# zulu_a7_6.net
KiCad netlist of a schematic drawn in Altium Designer
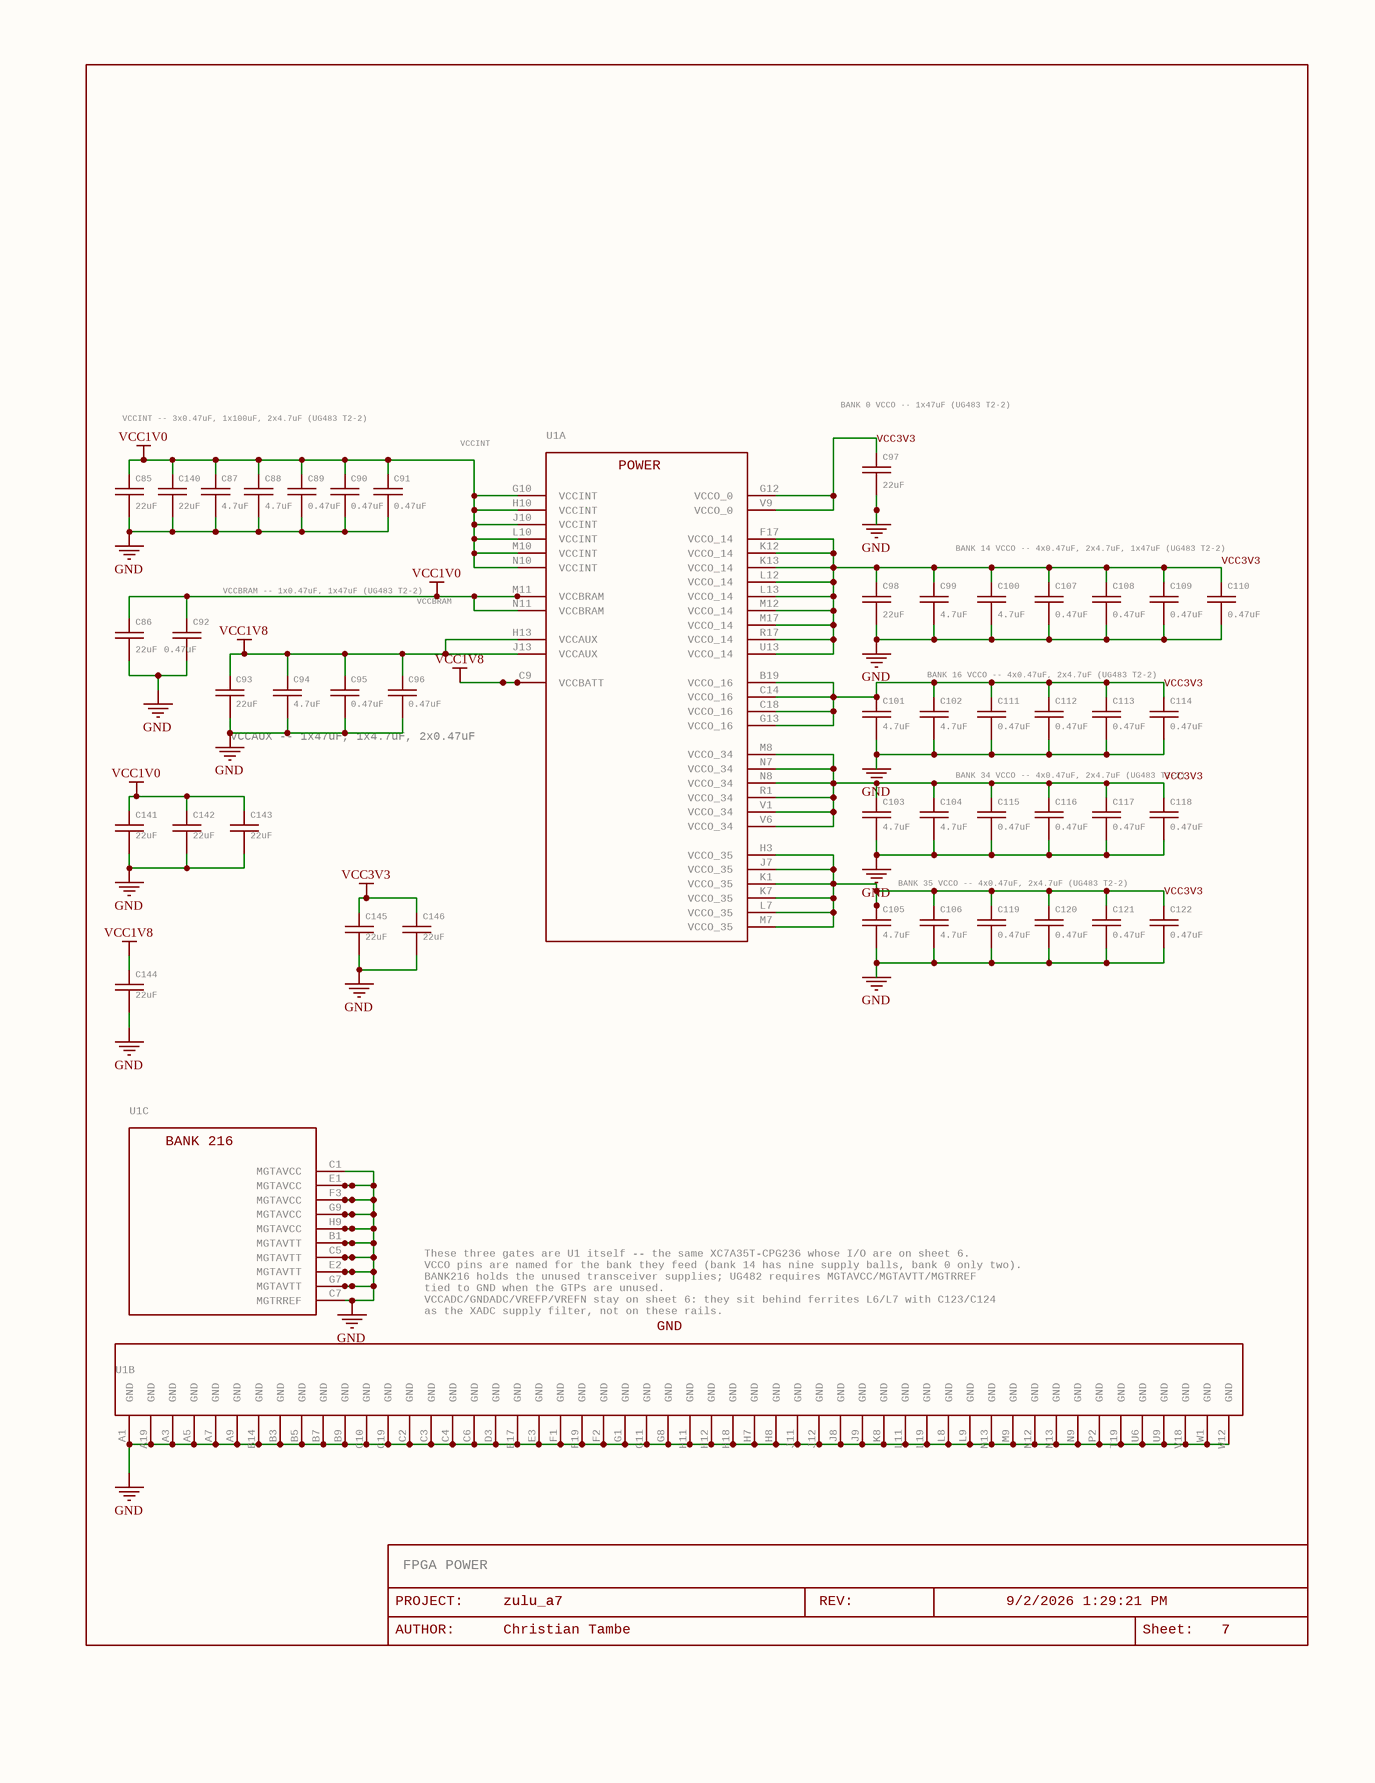
[diagram p0: zulu_a7_6.SchDoc]

(export (version "E")
  (design (tool "Eeschema 10.0.6"))
  (components
    (comp (ref "C85")
      (value "22uF")
      (footprint "C0805")
      (description "CAPACITOR, American symbol")
      (fields (field (name "MANF") "Murata"))
      (libsource (lib "") (part "C-USC0805_1"))
    )
    (comp (ref "C86")
      (value "22uF")
      (footprint "C0805")
      (description "CAPACITOR, American symbol")
      (fields (field (name "MANF") "Murata"))
      (libsource (lib "") (part "C-USC0805_1"))
    )
    (comp (ref "C87")
      (value "4.7uF")
      (footprint "C0603")
      (description "CAPACITOR, American symbol")
      (fields (field (name "MANF") "Murata"))
      (libsource (lib "rcl") (part "C-USC0603"))
    )
    (comp (ref "C88")
      (value "4.7uF")
      (footprint "C0603")
      (description "CAPACITOR, American symbol")
      (fields (field (name "MANF") "Murata"))
      (libsource (lib "rcl") (part "C-USC0603"))
    )
    (comp (ref "C89")
      (value "0.47uF")
      (footprint "C0201")
      (description "CAPACITOR, American symbol")
      (fields (field (name "MANF") "Murata"))
      (libsource (lib "rcl") (part "C-USC0201"))
    )
    (comp (ref "C90")
      (value "0.47uF")
      (footprint "C0201")
      (description "CAPACITOR, American symbol")
      (fields (field (name "MANF") "Murata"))
      (libsource (lib "rcl") (part "C-USC0201"))
    )
    (comp (ref "C91")
      (value "0.47uF")
      (footprint "C0201")
      (description "CAPACITOR, American symbol")
      (fields (field (name "MANF") "Murata"))
      (libsource (lib "rcl") (part "C-USC0201"))
    )
    (comp (ref "C92")
      (value "0.47uF")
      (footprint "C0201")
      (description "CAPACITOR, American symbol")
      (fields (field (name "MANF") "Murata"))
      (libsource (lib "rcl") (part "C-USC0201"))
    )
    (comp (ref "C93")
      (value "22uF")
      (footprint "C0805")
      (description "CAPACITOR, American symbol")
      (fields (field (name "MANF") "Murata"))
      (libsource (lib "") (part "C-USC0805_1"))
    )
    (comp (ref "C94")
      (value "4.7uF")
      (footprint "C0603")
      (description "CAPACITOR, American symbol")
      (fields (field (name "MANF") "Murata"))
      (libsource (lib "rcl") (part "C-USC0603"))
    )
    (comp (ref "C95")
      (value "0.47uF")
      (footprint "C0201")
      (description "CAPACITOR, American symbol")
      (fields (field (name "MANF") "Murata"))
      (libsource (lib "rcl") (part "C-USC0201"))
    )
    (comp (ref "C96")
      (value "0.47uF")
      (footprint "C0201")
      (description "CAPACITOR, American symbol")
      (fields (field (name "MANF") "Murata"))
      (libsource (lib "rcl") (part "C-USC0201"))
    )
    (comp (ref "C97")
      (value "22uF")
      (footprint "C0805")
      (description "CAPACITOR, American symbol")
      (fields (field (name "MANF") "Murata"))
      (libsource (lib "") (part "C-USC0805_1"))
    )
    (comp (ref "C98")
      (value "22uF")
      (footprint "C0805")
      (description "CAPACITOR, American symbol")
      (fields (field (name "MANF") "Murata"))
      (libsource (lib "") (part "C-USC0805_1"))
    )
    (comp (ref "C99")
      (value "4.7uF")
      (footprint "C0603")
      (description "CAPACITOR, American symbol")
      (fields (field (name "MANF") "Murata"))
      (libsource (lib "rcl") (part "C-USC0603"))
    )
    (comp (ref "C100")
      (value "4.7uF")
      (footprint "C0603")
      (description "CAPACITOR, American symbol")
      (fields (field (name "MANF") "Murata"))
      (libsource (lib "rcl") (part "C-USC0603"))
    )
    (comp (ref "C101")
      (value "4.7uF")
      (footprint "C0603")
      (description "CAPACITOR, American symbol")
      (fields (field (name "MANF") "Murata"))
      (libsource (lib "rcl") (part "C-USC0603"))
    )
    (comp (ref "C102")
      (value "4.7uF")
      (footprint "C0603")
      (description "CAPACITOR, American symbol")
      (fields (field (name "MANF") "Murata"))
      (libsource (lib "rcl") (part "C-USC0603"))
    )
    (comp (ref "C103")
      (value "4.7uF")
      (footprint "C0603")
      (description "CAPACITOR, American symbol")
      (fields (field (name "MANF") "Murata"))
      (libsource (lib "rcl") (part "C-USC0603"))
    )
    (comp (ref "C104")
      (value "4.7uF")
      (footprint "C0603")
      (description "CAPACITOR, American symbol")
      (fields (field (name "MANF") "Murata"))
      (libsource (lib "rcl") (part "C-USC0603"))
    )
    (comp (ref "C105")
      (value "4.7uF")
      (footprint "C0603")
      (description "CAPACITOR, American symbol")
      (fields (field (name "MANF") "Murata"))
      (libsource (lib "rcl") (part "C-USC0603"))
    )
    (comp (ref "C106")
      (value "4.7uF")
      (footprint "C0603")
      (description "CAPACITOR, American symbol")
      (fields (field (name "MANF") "Murata"))
      (libsource (lib "rcl") (part "C-USC0603"))
    )
    (comp (ref "C107")
      (value "0.47uF")
      (footprint "C0201")
      (description "CAPACITOR, American symbol")
      (fields (field (name "MANF") "Murata"))
      (libsource (lib "rcl") (part "C-USC0201"))
    )
    (comp (ref "C108")
      (value "0.47uF")
      (footprint "C0201")
      (description "CAPACITOR, American symbol")
      (fields (field (name "MANF") "Murata"))
      (libsource (lib "rcl") (part "C-USC0201"))
    )
    (comp (ref "C109")
      (value "0.47uF")
      (footprint "C0201")
      (description "CAPACITOR, American symbol")
      (fields (field (name "MANF") "Murata"))
      (libsource (lib "rcl") (part "C-USC0201"))
    )
    (comp (ref "C110")
      (value "0.47uF")
      (footprint "C0201")
      (description "CAPACITOR, American symbol")
      (fields (field (name "MANF") "Murata"))
      (libsource (lib "rcl") (part "C-USC0201"))
    )
    (comp (ref "C111")
      (value "0.47uF")
      (footprint "C0201")
      (description "CAPACITOR, American symbol")
      (fields (field (name "MANF") "Murata"))
      (libsource (lib "rcl") (part "C-USC0201"))
    )
    (comp (ref "C112")
      (value "0.47uF")
      (footprint "C0201")
      (description "CAPACITOR, American symbol")
      (fields (field (name "MANF") "Murata"))
      (libsource (lib "rcl") (part "C-USC0201"))
    )
    (comp (ref "C113")
      (value "0.47uF")
      (footprint "C0201")
      (description "CAPACITOR, American symbol")
      (fields (field (name "MANF") "Murata"))
      (libsource (lib "rcl") (part "C-USC0201"))
    )
    (comp (ref "C114")
      (value "0.47uF")
      (footprint "C0201")
      (description "CAPACITOR, American symbol")
      (fields (field (name "MANF") "Murata"))
      (libsource (lib "rcl") (part "C-USC0201"))
    )
    (comp (ref "C115")
      (value "0.47uF")
      (footprint "C0201")
      (description "CAPACITOR, American symbol")
      (fields (field (name "MANF") "Murata"))
      (libsource (lib "rcl") (part "C-USC0201"))
    )
    (comp (ref "C116")
      (value "0.47uF")
      (footprint "C0201")
      (description "CAPACITOR, American symbol")
      (fields (field (name "MANF") "Murata"))
      (libsource (lib "rcl") (part "C-USC0201"))
    )
    (comp (ref "C117")
      (value "0.47uF")
      (footprint "C0201")
      (description "CAPACITOR, American symbol")
      (fields (field (name "MANF") "Murata"))
      (libsource (lib "rcl") (part "C-USC0201"))
    )
    (comp (ref "C118")
      (value "0.47uF")
      (footprint "C0201")
      (description "CAPACITOR, American symbol")
      (fields (field (name "MANF") "Murata"))
      (libsource (lib "rcl") (part "C-USC0201"))
    )
    (comp (ref "C119")
      (value "0.47uF")
      (footprint "C0201")
      (description "CAPACITOR, American symbol")
      (fields (field (name "MANF") "Murata"))
      (libsource (lib "rcl") (part "C-USC0201"))
    )
    (comp (ref "C120")
      (value "0.47uF")
      (footprint "C0201")
      (description "CAPACITOR, American symbol")
      (fields (field (name "MANF") "Murata"))
      (libsource (lib "rcl") (part "C-USC0201"))
    )
    (comp (ref "C121")
      (value "0.47uF")
      (footprint "C0201")
      (description "CAPACITOR, American symbol")
      (fields (field (name "MANF") "Murata"))
      (libsource (lib "rcl") (part "C-USC0201"))
    )
    (comp (ref "C122")
      (value "0.47uF")
      (footprint "C0201")
      (description "CAPACITOR, American symbol")
      (fields (field (name "MANF") "Murata"))
      (libsource (lib "rcl") (part "C-USC0201"))
    )
    (comp (ref "C140")
      (value "22uF")
      (footprint "C0805")
      (description "CAPACITOR, American symbol")
      (fields (field (name "MANF") "Murata"))
      (libsource (lib "") (part "C-USC0805_1"))
    )
    (comp (ref "C141")
      (value "22uF")
      (footprint "C0805")
      (description "CAPACITOR, American symbol")
      (fields (field (name "MANF") "Murata"))
      (libsource (lib "") (part "C-USC0805_1"))
    )
    (comp (ref "C142")
      (value "22uF")
      (footprint "C0805")
      (description "CAPACITOR, American symbol")
      (fields (field (name "MANF") "Murata"))
      (libsource (lib "") (part "C-USC0805_1"))
    )
    (comp (ref "C143")
      (value "22uF")
      (footprint "C0805")
      (description "CAPACITOR, American symbol")
      (fields (field (name "MANF") "Murata"))
      (libsource (lib "") (part "C-USC0805_1"))
    )
    (comp (ref "C144")
      (value "22uF")
      (footprint "C0805")
      (description "CAPACITOR, American symbol")
      (fields (field (name "MANF") "Murata"))
      (libsource (lib "") (part "C-USC0805_2"))
    )
    (comp (ref "C145")
      (value "22uF")
      (footprint "C0805")
      (description "CAPACITOR, American symbol")
      (fields (field (name "MANF") "Murata"))
      (libsource (lib "rcl") (part "C-USC0805"))
    )
    (comp (ref "C146")
      (value "22uF")
      (footprint "C0805")
      (description "CAPACITOR, American symbol")
      (fields (field (name "MANF") "Murata"))
      (libsource (lib "rcl") (part "C-USC0805"))
    )
    (comp (ref "FRAME6")
      (value "DOCFIELD")
      (description "DOCUMENT FIELD")
      (fields
        (field (name "LAST_DATE_TIME") "9/2/2026 1:29:21 PM")
        (field (name "SHEET") "Sheet:")
        (field (name "SHEET_1") "7")
        (field (name "REV") "REV:")
        (field (name "PROJECT") "PROJECT:")
        (field (name "DRAWING_NAME") "zulu_a7")
        (field (name "AUTHOR") "Christian Tambe")
        (field (name "DRAWING_NAME_1") "zulu_a7")
        (field (name "SHEET_2") "7")
        (field (name "LIBRARYNAME") "ctambe")
      )
      (libsource (lib "ctambe") (part "DOCFIELD"))
    )
    (comp (ref "U1")
      (value "XC7A35T-1CPG236C")
      (footprint "XC7A35T-CPG236")
      (fields
        (field (name "BANK216") "BANK 216")
        (field (name "MANF") "AMD/Xilinx")
        (field (name "GND") "GND")
        (field (name "POWER") "POWER")
        (field (name "LIBRARYNAME") "ctambe")
      )
      (libsource (lib "ctambe") (part "XC7A35T-CPG236-1CPG236C"))
    )
  )
  (nets
    (net (code "1") (name "GND") (class "Default")
      (node (ref "C100") (pin "2") (pinfunction "2_2") (pintype "passive"))
      (node (ref "C101") (pin "2") (pinfunction "2_2") (pintype "passive"))
      (node (ref "C102") (pin "2") (pinfunction "2_2") (pintype "passive"))
      (node (ref "C103") (pin "2") (pinfunction "2_2") (pintype "passive"))
      (node (ref "C104") (pin "2") (pinfunction "2_2") (pintype "passive"))
      (node (ref "C105") (pin "2") (pinfunction "2_2") (pintype "passive"))
      (node (ref "C106") (pin "2") (pinfunction "2_2") (pintype "passive"))
      (node (ref "C107") (pin "2") (pinfunction "2_2") (pintype "passive"))
      (node (ref "C108") (pin "2") (pinfunction "2_2") (pintype "passive"))
      (node (ref "C109") (pin "2") (pinfunction "2_2") (pintype "passive"))
      (node (ref "C110") (pin "2") (pinfunction "2_2") (pintype "passive"))
      (node (ref "C111") (pin "2") (pinfunction "2_2") (pintype "passive"))
      (node (ref "C112") (pin "2") (pinfunction "2_2") (pintype "passive"))
      (node (ref "C113") (pin "2") (pinfunction "2_2") (pintype "passive"))
      (node (ref "C114") (pin "2") (pinfunction "2_2") (pintype "passive"))
      (node (ref "C115") (pin "2") (pinfunction "2_2") (pintype "passive"))
      (node (ref "C116") (pin "2") (pinfunction "2_2") (pintype "passive"))
      (node (ref "C117") (pin "2") (pinfunction "2_2") (pintype "passive"))
      (node (ref "C118") (pin "2") (pinfunction "2_2") (pintype "passive"))
      (node (ref "C119") (pin "2") (pinfunction "2_2") (pintype "passive"))
      (node (ref "C120") (pin "2") (pinfunction "2_2") (pintype "passive"))
      (node (ref "C121") (pin "2") (pinfunction "2_2") (pintype "passive"))
      (node (ref "C122") (pin "2") (pinfunction "2_2") (pintype "passive"))
      (node (ref "C140") (pin "2") (pinfunction "2_2") (pintype "passive"))
      (node (ref "C141") (pin "2") (pinfunction "2_2") (pintype "passive"))
      (node (ref "C142") (pin "2") (pinfunction "2_2") (pintype "passive"))
      (node (ref "C143") (pin "2") (pinfunction "2_2") (pintype "passive"))
      (node (ref "C144") (pin "2") (pinfunction "2_2") (pintype "passive"))
      (node (ref "C145") (pin "2") (pinfunction "2_2") (pintype "passive"))
      (node (ref "C146") (pin "2") (pinfunction "2_2") (pintype "passive"))
      (node (ref "C85") (pin "2") (pinfunction "2_2") (pintype "passive"))
      (node (ref "C86") (pin "2") (pinfunction "2_2") (pintype "passive"))
      (node (ref "C87") (pin "2") (pinfunction "2_2") (pintype "passive"))
      (node (ref "C88") (pin "2") (pinfunction "2_2") (pintype "passive"))
      (node (ref "C89") (pin "2") (pinfunction "2_2") (pintype "passive"))
      (node (ref "C90") (pin "2") (pinfunction "2_2") (pintype "passive"))
      (node (ref "C91") (pin "2") (pinfunction "2_2") (pintype "passive"))
      (node (ref "C92") (pin "2") (pinfunction "2_2") (pintype "passive"))
      (node (ref "C93") (pin "2") (pinfunction "2_2") (pintype "passive"))
      (node (ref "C94") (pin "2") (pinfunction "2_2") (pintype "passive"))
      (node (ref "C95") (pin "2") (pinfunction "2_2") (pintype "passive"))
      (node (ref "C96") (pin "2") (pinfunction "2_2") (pintype "passive"))
      (node (ref "C97") (pin "2") (pinfunction "2_2") (pintype "passive"))
      (node (ref "C98") (pin "2") (pinfunction "2_2") (pintype "passive"))
      (node (ref "C99") (pin "2") (pinfunction "2_2") (pintype "passive"))
      (node (ref "U1") (pin "A1") (pinfunction "GND_A1") (pintype "power_in"))
      (node (ref "U1") (pin "A19") (pinfunction "GND_A19") (pintype "power_in"))
      (node (ref "U1") (pin "A3") (pinfunction "GND_A3") (pintype "power_in"))
      (node (ref "U1") (pin "A5") (pinfunction "GND_A5") (pintype "power_in"))
      (node (ref "U1") (pin "A7") (pinfunction "GND_A7") (pintype "power_in"))
      (node (ref "U1") (pin "A9") (pinfunction "GND_A9") (pintype "power_in"))
      (node (ref "U1") (pin "B1") (pinfunction "MGTAVTT_B1") (pintype "power_in"))
      (node (ref "U1") (pin "B14") (pinfunction "GND_B14") (pintype "power_in"))
      (node (ref "U1") (pin "B3") (pinfunction "GND_B3") (pintype "power_in"))
      (node (ref "U1") (pin "B5") (pinfunction "GND_B5") (pintype "power_in"))
      (node (ref "U1") (pin "B7") (pinfunction "GND_B7") (pintype "power_in"))
      (node (ref "U1") (pin "B9") (pinfunction "GND_B9") (pintype "power_in"))
      (node (ref "U1") (pin "C1") (pinfunction "MGTAVCC_C1") (pintype "power_in"))
      (node (ref "U1") (pin "C10") (pinfunction "GND_C10") (pintype "power_in"))
      (node (ref "U1") (pin "C19") (pinfunction "GND_C19") (pintype "power_in"))
      (node (ref "U1") (pin "C2") (pinfunction "GND_C2") (pintype "power_in"))
      (node (ref "U1") (pin "C3") (pinfunction "GND_C3") (pintype "power_in"))
      (node (ref "U1") (pin "C4") (pinfunction "GND_C4") (pintype "power_in"))
      (node (ref "U1") (pin "C5") (pinfunction "MGTAVTT_C5") (pintype "power_in"))
      (node (ref "U1") (pin "C6") (pinfunction "GND_C6") (pintype "power_in"))
      (node (ref "U1") (pin "C7") (pinfunction "MGTRREF_C7") (pintype "power_in"))
      (node (ref "U1") (pin "D3") (pinfunction "GND_D3") (pintype "power_in"))
      (node (ref "U1") (pin "E1") (pinfunction "MGTAVCC_E1") (pintype "power_in"))
      (node (ref "U1") (pin "E17") (pinfunction "GND_E17") (pintype "power_in"))
      (node (ref "U1") (pin "E2") (pinfunction "MGTAVTT_E2") (pintype "power_in"))
      (node (ref "U1") (pin "E3") (pinfunction "GND_E3") (pintype "power_in"))
      (node (ref "U1") (pin "F1") (pinfunction "GND_F1") (pintype "power_in"))
      (node (ref "U1") (pin "F19") (pinfunction "GND_F19") (pintype "power_in"))
      (node (ref "U1") (pin "F2") (pinfunction "GND_F2") (pintype "power_in"))
      (node (ref "U1") (pin "F3") (pinfunction "MGTAVCC_F3") (pintype "power_in"))
      (node (ref "U1") (pin "G1") (pinfunction "GND_G1") (pintype "power_in"))
      (node (ref "U1") (pin "G11") (pinfunction "GND_G11") (pintype "power_in"))
      (node (ref "U1") (pin "G7") (pinfunction "MGTAVTT_G7") (pintype "power_in"))
      (node (ref "U1") (pin "G8") (pinfunction "GND_G8") (pintype "power_in"))
      (node (ref "U1") (pin "G9") (pinfunction "MGTAVCC_G9") (pintype "power_in"))
      (node (ref "U1") (pin "H11") (pinfunction "GND_H11") (pintype "power_in"))
      (node (ref "U1") (pin "H12") (pinfunction "GND_H12") (pintype "power_in"))
      (node (ref "U1") (pin "H18") (pinfunction "GND_H18") (pintype "power_in"))
      (node (ref "U1") (pin "H7") (pinfunction "GND_H7") (pintype "power_in"))
      (node (ref "U1") (pin "H8") (pinfunction "GND_H8") (pintype "power_in"))
      (node (ref "U1") (pin "H9") (pinfunction "MGTAVCC_H9") (pintype "power_in"))
      (node (ref "U1") (pin "J11") (pinfunction "GND_J11") (pintype "power_in"))
      (node (ref "U1") (pin "J12") (pinfunction "GND_J12") (pintype "power_in"))
      (node (ref "U1") (pin "J8") (pinfunction "GND_J8") (pintype "power_in"))
      (node (ref "U1") (pin "J9") (pinfunction "GND_J9") (pintype "power_in"))
      (node (ref "U1") (pin "K8") (pinfunction "GND_K8") (pintype "power_in"))
      (node (ref "U1") (pin "L11") (pinfunction "GND_L11") (pintype "power_in"))
      (node (ref "U1") (pin "L19") (pinfunction "GND_L19") (pintype "power_in"))
      (node (ref "U1") (pin "L8") (pinfunction "GND_L8") (pintype "power_in"))
      (node (ref "U1") (pin "L9") (pinfunction "GND_L9") (pintype "power_in"))
      (node (ref "U1") (pin "M13") (pinfunction "GND_M13") (pintype "power_in"))
      (node (ref "U1") (pin "M9") (pinfunction "GND_M9") (pintype "power_in"))
      (node (ref "U1") (pin "N12") (pinfunction "GND_N12") (pintype "power_in"))
      (node (ref "U1") (pin "N13") (pinfunction "GND_N13") (pintype "power_in"))
      (node (ref "U1") (pin "N9") (pinfunction "GND_N9") (pintype "power_in"))
      (node (ref "U1") (pin "P2") (pinfunction "GND_P2") (pintype "power_in"))
      (node (ref "U1") (pin "T19") (pinfunction "GND_T19") (pintype "power_in"))
      (node (ref "U1") (pin "U6") (pinfunction "GND_U6") (pintype "power_in"))
      (node (ref "U1") (pin "U9") (pinfunction "GND_U9") (pintype "power_in"))
      (node (ref "U1") (pin "V18") (pinfunction "GND_V18") (pintype "power_in"))
      (node (ref "U1") (pin "W1") (pinfunction "GND_W1") (pintype "power_in"))
      (node (ref "U1") (pin "W12") (pinfunction "GND_W12") (pintype "power_in"))
    )
    (net (code "2") (name "VCC1V0") (class "Default")
      (node (ref "C140") (pin "1") (pinfunction "1_1") (pintype "passive"))
      (node (ref "C141") (pin "1") (pinfunction "1_1") (pintype "passive"))
      (node (ref "C142") (pin "1") (pinfunction "1_1") (pintype "passive"))
      (node (ref "C143") (pin "1") (pinfunction "1_1") (pintype "passive"))
      (node (ref "C85") (pin "1") (pinfunction "1_1") (pintype "passive"))
      (node (ref "C86") (pin "1") (pinfunction "1_1") (pintype "passive"))
      (node (ref "C87") (pin "1") (pinfunction "1_1") (pintype "passive"))
      (node (ref "C88") (pin "1") (pinfunction "1_1") (pintype "passive"))
      (node (ref "C89") (pin "1") (pinfunction "1_1") (pintype "passive"))
      (node (ref "C90") (pin "1") (pinfunction "1_1") (pintype "passive"))
      (node (ref "C91") (pin "1") (pinfunction "1_1") (pintype "passive"))
      (node (ref "C92") (pin "1") (pinfunction "1_1") (pintype "passive"))
      (node (ref "U1") (pin "G10") (pinfunction "VCCINT_G10") (pintype "power_in"))
      (node (ref "U1") (pin "H10") (pinfunction "VCCINT_H10") (pintype "power_in"))
      (node (ref "U1") (pin "J10") (pinfunction "VCCINT_J10") (pintype "power_in"))
      (node (ref "U1") (pin "L10") (pinfunction "VCCINT_L10") (pintype "power_in"))
      (node (ref "U1") (pin "M10") (pinfunction "VCCINT_M10") (pintype "power_in"))
      (node (ref "U1") (pin "M11") (pinfunction "VCCBRAM_M11") (pintype "power_in"))
      (node (ref "U1") (pin "N10") (pinfunction "VCCINT_N10") (pintype "power_in"))
      (node (ref "U1") (pin "N11") (pinfunction "VCCBRAM_N11") (pintype "power_in"))
    )
    (net (code "3") (name "VCC1V8") (class "Default")
      (node (ref "C144") (pin "1") (pinfunction "1_1") (pintype "passive"))
      (node (ref "C93") (pin "1") (pinfunction "1_1") (pintype "passive"))
      (node (ref "C94") (pin "1") (pinfunction "1_1") (pintype "passive"))
      (node (ref "C95") (pin "1") (pinfunction "1_1") (pintype "passive"))
      (node (ref "C96") (pin "1") (pinfunction "1_1") (pintype "passive"))
      (node (ref "U1") (pin "C9") (pinfunction "VCCBATT_C9") (pintype "power_in"))
      (node (ref "U1") (pin "H13") (pinfunction "VCCAUX_H13") (pintype "power_in"))
      (node (ref "U1") (pin "J13") (pinfunction "VCCAUX_J13") (pintype "power_in"))
    )
    (net (code "4") (name "VCC3V3") (class "Default")
      (node (ref "C100") (pin "1") (pinfunction "1_1") (pintype "passive"))
      (node (ref "C101") (pin "1") (pinfunction "1_1") (pintype "passive"))
      (node (ref "C102") (pin "1") (pinfunction "1_1") (pintype "passive"))
      (node (ref "C103") (pin "1") (pinfunction "1_1") (pintype "passive"))
      (node (ref "C104") (pin "1") (pinfunction "1_1") (pintype "passive"))
      (node (ref "C105") (pin "1") (pinfunction "1_1") (pintype "passive"))
      (node (ref "C106") (pin "1") (pinfunction "1_1") (pintype "passive"))
      (node (ref "C107") (pin "1") (pinfunction "1_1") (pintype "passive"))
      (node (ref "C108") (pin "1") (pinfunction "1_1") (pintype "passive"))
      (node (ref "C109") (pin "1") (pinfunction "1_1") (pintype "passive"))
      (node (ref "C110") (pin "1") (pinfunction "1_1") (pintype "passive"))
      (node (ref "C111") (pin "1") (pinfunction "1_1") (pintype "passive"))
      (node (ref "C112") (pin "1") (pinfunction "1_1") (pintype "passive"))
      (node (ref "C113") (pin "1") (pinfunction "1_1") (pintype "passive"))
      (node (ref "C114") (pin "1") (pinfunction "1_1") (pintype "passive"))
      (node (ref "C115") (pin "1") (pinfunction "1_1") (pintype "passive"))
      (node (ref "C116") (pin "1") (pinfunction "1_1") (pintype "passive"))
      (node (ref "C117") (pin "1") (pinfunction "1_1") (pintype "passive"))
      (node (ref "C118") (pin "1") (pinfunction "1_1") (pintype "passive"))
      (node (ref "C119") (pin "1") (pinfunction "1_1") (pintype "passive"))
      (node (ref "C120") (pin "1") (pinfunction "1_1") (pintype "passive"))
      (node (ref "C121") (pin "1") (pinfunction "1_1") (pintype "passive"))
      (node (ref "C122") (pin "1") (pinfunction "1_1") (pintype "passive"))
      (node (ref "C145") (pin "1") (pinfunction "1_1") (pintype "passive"))
      (node (ref "C146") (pin "1") (pinfunction "1_1") (pintype "passive"))
      (node (ref "C97") (pin "1") (pinfunction "1_1") (pintype "passive"))
      (node (ref "C98") (pin "1") (pinfunction "1_1") (pintype "passive"))
      (node (ref "C99") (pin "1") (pinfunction "1_1") (pintype "passive"))
      (node (ref "U1") (pin "B19") (pinfunction "VCCO_16_B19") (pintype "power_in"))
      (node (ref "U1") (pin "C14") (pinfunction "VCCO_16_C14") (pintype "power_in"))
      (node (ref "U1") (pin "C18") (pinfunction "VCCO_16_C18") (pintype "power_in"))
      (node (ref "U1") (pin "F17") (pinfunction "VCCO_14_F17") (pintype "power_in"))
      (node (ref "U1") (pin "G12") (pinfunction "VCCO_0_G12") (pintype "power_in"))
      (node (ref "U1") (pin "G13") (pinfunction "VCCO_16_G13") (pintype "power_in"))
      (node (ref "U1") (pin "H3") (pinfunction "VCCO_35_H3") (pintype "power_in"))
      (node (ref "U1") (pin "J7") (pinfunction "VCCO_35_J7") (pintype "power_in"))
      (node (ref "U1") (pin "K1") (pinfunction "VCCO_35_K1") (pintype "power_in"))
      (node (ref "U1") (pin "K12") (pinfunction "VCCO_14_K12") (pintype "power_in"))
      (node (ref "U1") (pin "K13") (pinfunction "VCCO_14_K13") (pintype "power_in"))
      (node (ref "U1") (pin "K7") (pinfunction "VCCO_35_K7") (pintype "power_in"))
      (node (ref "U1") (pin "L12") (pinfunction "VCCO_14_L12") (pintype "power_in"))
      (node (ref "U1") (pin "L13") (pinfunction "VCCO_14_L13") (pintype "power_in"))
      (node (ref "U1") (pin "L7") (pinfunction "VCCO_35_L7") (pintype "power_in"))
      (node (ref "U1") (pin "M12") (pinfunction "VCCO_14_M12") (pintype "power_in"))
      (node (ref "U1") (pin "M17") (pinfunction "VCCO_14_M17") (pintype "power_in"))
      (node (ref "U1") (pin "M7") (pinfunction "VCCO_35_M7") (pintype "power_in"))
      (node (ref "U1") (pin "M8") (pinfunction "VCCO_34_M8") (pintype "power_in"))
      (node (ref "U1") (pin "N7") (pinfunction "VCCO_34_N7") (pintype "power_in"))
      (node (ref "U1") (pin "N8") (pinfunction "VCCO_34_N8") (pintype "power_in"))
      (node (ref "U1") (pin "R1") (pinfunction "VCCO_34_R1") (pintype "power_in"))
      (node (ref "U1") (pin "R17") (pinfunction "VCCO_14_R17") (pintype "power_in"))
      (node (ref "U1") (pin "U13") (pinfunction "VCCO_14_U13") (pintype "power_in"))
      (node (ref "U1") (pin "V1") (pinfunction "VCCO_34_V1") (pintype "power_in"))
      (node (ref "U1") (pin "V6") (pinfunction "VCCO_34_V6") (pintype "power_in"))
      (node (ref "U1") (pin "V9") (pinfunction "VCCO_0_V9") (pintype "power_in"))
    )
  )
)
